# touch_555_mini.net
KiCad netlist of a schematic drawn in EAGLE
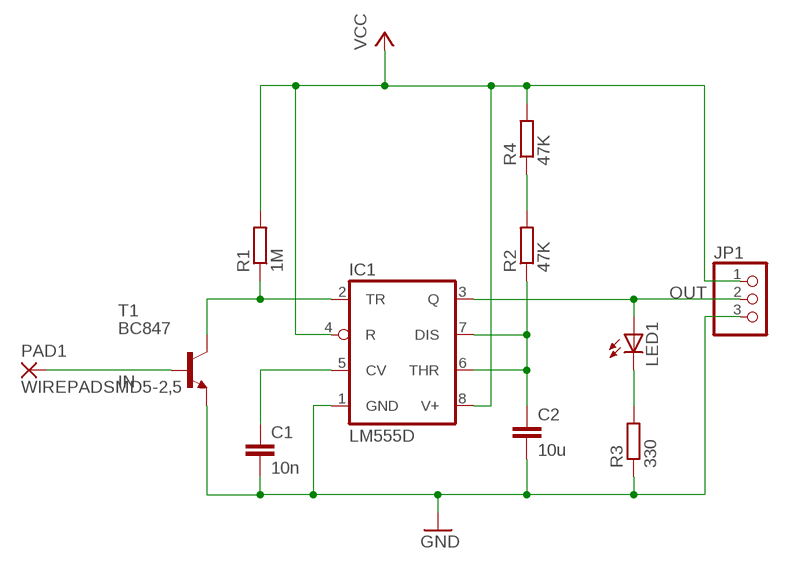
[diagram p0: schematic, sheet 1]

(export (version "E")
  (design (tool "Eeschema 10.0.6"))
  (components
    (comp (ref "C1")
      (value "10n")
      (footprint "eagle-import:C0805")
      (libsource (lib "eagle-import") (part "C-EUC0805"))
    )
    (comp (ref "C2")
      (value "10u")
      (footprint "eagle-import:C0805")
      (libsource (lib "eagle-import") (part "C-EUC0805"))
    )
    (comp (ref "IC1")
      (value "LM555D")
      (footprint "eagle-import:SO08")
      (libsource (lib "eagle-import") (part "555DLM"))
    )
    (comp (ref "JP1")
      (value "PINHD-1X3")
      (footprint "eagle-import:1X03")
      (libsource (lib "eagle-import") (part "PINHD-1X3"))
    )
    (comp (ref "LED1")
      (value "LEDCHIPLED_1206")
      (footprint "eagle-import:CHIPLED_1206")
      (libsource (lib "eagle-import") (part "LEDCHIPLED_1206"))
    )
    (comp (ref "PAD1")
      (value "WIREPADSMD5-2,5")
      (footprint "eagle-import:5-2,5")
      (libsource (lib "eagle-import") (part "WIREPADSMD5-2,5"))
    )
    (comp (ref "R1")
      (value "1M")
      (footprint "eagle-import:R0805")
      (libsource (lib "eagle-import") (part "R-EU_R0805"))
    )
    (comp (ref "R2")
      (value "47K")
      (footprint "eagle-import:R0805")
      (libsource (lib "eagle-import") (part "R-EU_R0805"))
    )
    (comp (ref "R3")
      (value "330")
      (footprint "eagle-import:R0805")
      (libsource (lib "eagle-import") (part "R-EU_R0805"))
    )
    (comp (ref "R4")
      (value "47K")
      (footprint "eagle-import:R0805")
      (libsource (lib "eagle-import") (part "R-EU_R0805"))
    )
    (comp (ref "T1")
      (value "BC847")
      (footprint "eagle-import:SOT23")
      (libsource (lib "eagle-import") (part "BC847"))
    )
  )
  (nets
    (net (code "1") (name "/IN") (class "Default")
      (node (ref "PAD1") (pin "1") (pinfunction "P_1") (pintype "passive"))
      (node (ref "T1") (pin "1") (pinfunction "B_1") (pintype "passive"))
    )
    (net (code "2") (name "/OUT") (class "Default")
      (node (ref "IC1") (pin "3") (pinfunction "Q_3") (pintype "output"))
      (node (ref "JP1") (pin "2") (pinfunction "2_2") (pintype "passive"))
      (node (ref "LED1") (pin "A") (pinfunction "A_A") (pintype "passive"))
    )
    (net (code "3") (name "GND") (class "Default")
      (node (ref "C1") (pin "2") (pinfunction "2_2") (pintype "passive"))
      (node (ref "C2") (pin "2") (pinfunction "2_2") (pintype "passive"))
      (node (ref "IC1") (pin "1") (pinfunction "GND_1") (pintype "power_in"))
      (node (ref "JP1") (pin "3") (pinfunction "3_3") (pintype "passive"))
      (node (ref "R3") (pin "1") (pinfunction "1_1") (pintype "passive"))
      (node (ref "T1") (pin "2") (pinfunction "E_2") (pintype "passive"))
    )
    (net (code "4") (name "Net-(IC1-CV)") (class "Default")
      (node (ref "C1") (pin "1") (pinfunction "1_1") (pintype "passive"))
      (node (ref "IC1") (pin "5") (pinfunction "CV_5") (pintype "input"))
    )
    (net (code "5") (name "Net-(IC1-DIS)") (class "Default")
      (node (ref "C2") (pin "1") (pinfunction "1_1") (pintype "passive"))
      (node (ref "IC1") (pin "6") (pinfunction "THR_6") (pintype "input"))
      (node (ref "IC1") (pin "7") (pinfunction "DIS_7") (pintype "input"))
      (node (ref "R2") (pin "1") (pinfunction "1_1") (pintype "passive"))
    )
    (net (code "6") (name "Net-(IC1-TR)") (class "Default")
      (node (ref "IC1") (pin "2") (pinfunction "TR_2") (pintype "input"))
      (node (ref "R1") (pin "1") (pinfunction "1_1") (pintype "passive"))
      (node (ref "T1") (pin "3") (pinfunction "C_3") (pintype "passive"))
    )
    (net (code "7") (name "Net-(LED1-PadC)") (class "Default")
      (node (ref "LED1") (pin "C") (pinfunction "C_C") (pintype "passive"))
      (node (ref "R3") (pin "2") (pinfunction "2_2") (pintype "passive"))
    )
    (net (code "8") (name "Net-(R2-Pad2)") (class "Default")
      (node (ref "R2") (pin "2") (pinfunction "2_2") (pintype "passive"))
      (node (ref "R4") (pin "1") (pinfunction "1_1") (pintype "passive"))
    )
    (net (code "9") (name "VCC") (class "Default")
      (node (ref "IC1") (pin "4") (pinfunction "R_4") (pintype "input"))
      (node (ref "IC1") (pin "8") (pinfunction "V+_8") (pintype "power_in"))
      (node (ref "JP1") (pin "1") (pinfunction "1_1") (pintype "passive"))
      (node (ref "R1") (pin "2") (pinfunction "2_2") (pintype "passive"))
      (node (ref "R4") (pin "2") (pinfunction "2_2") (pintype "passive"))
    )
  )
)
